# DM1098LUXD-LITE_LEFT_OV7251.net
KiCad netlist of a schematic drawn in Altium Designer
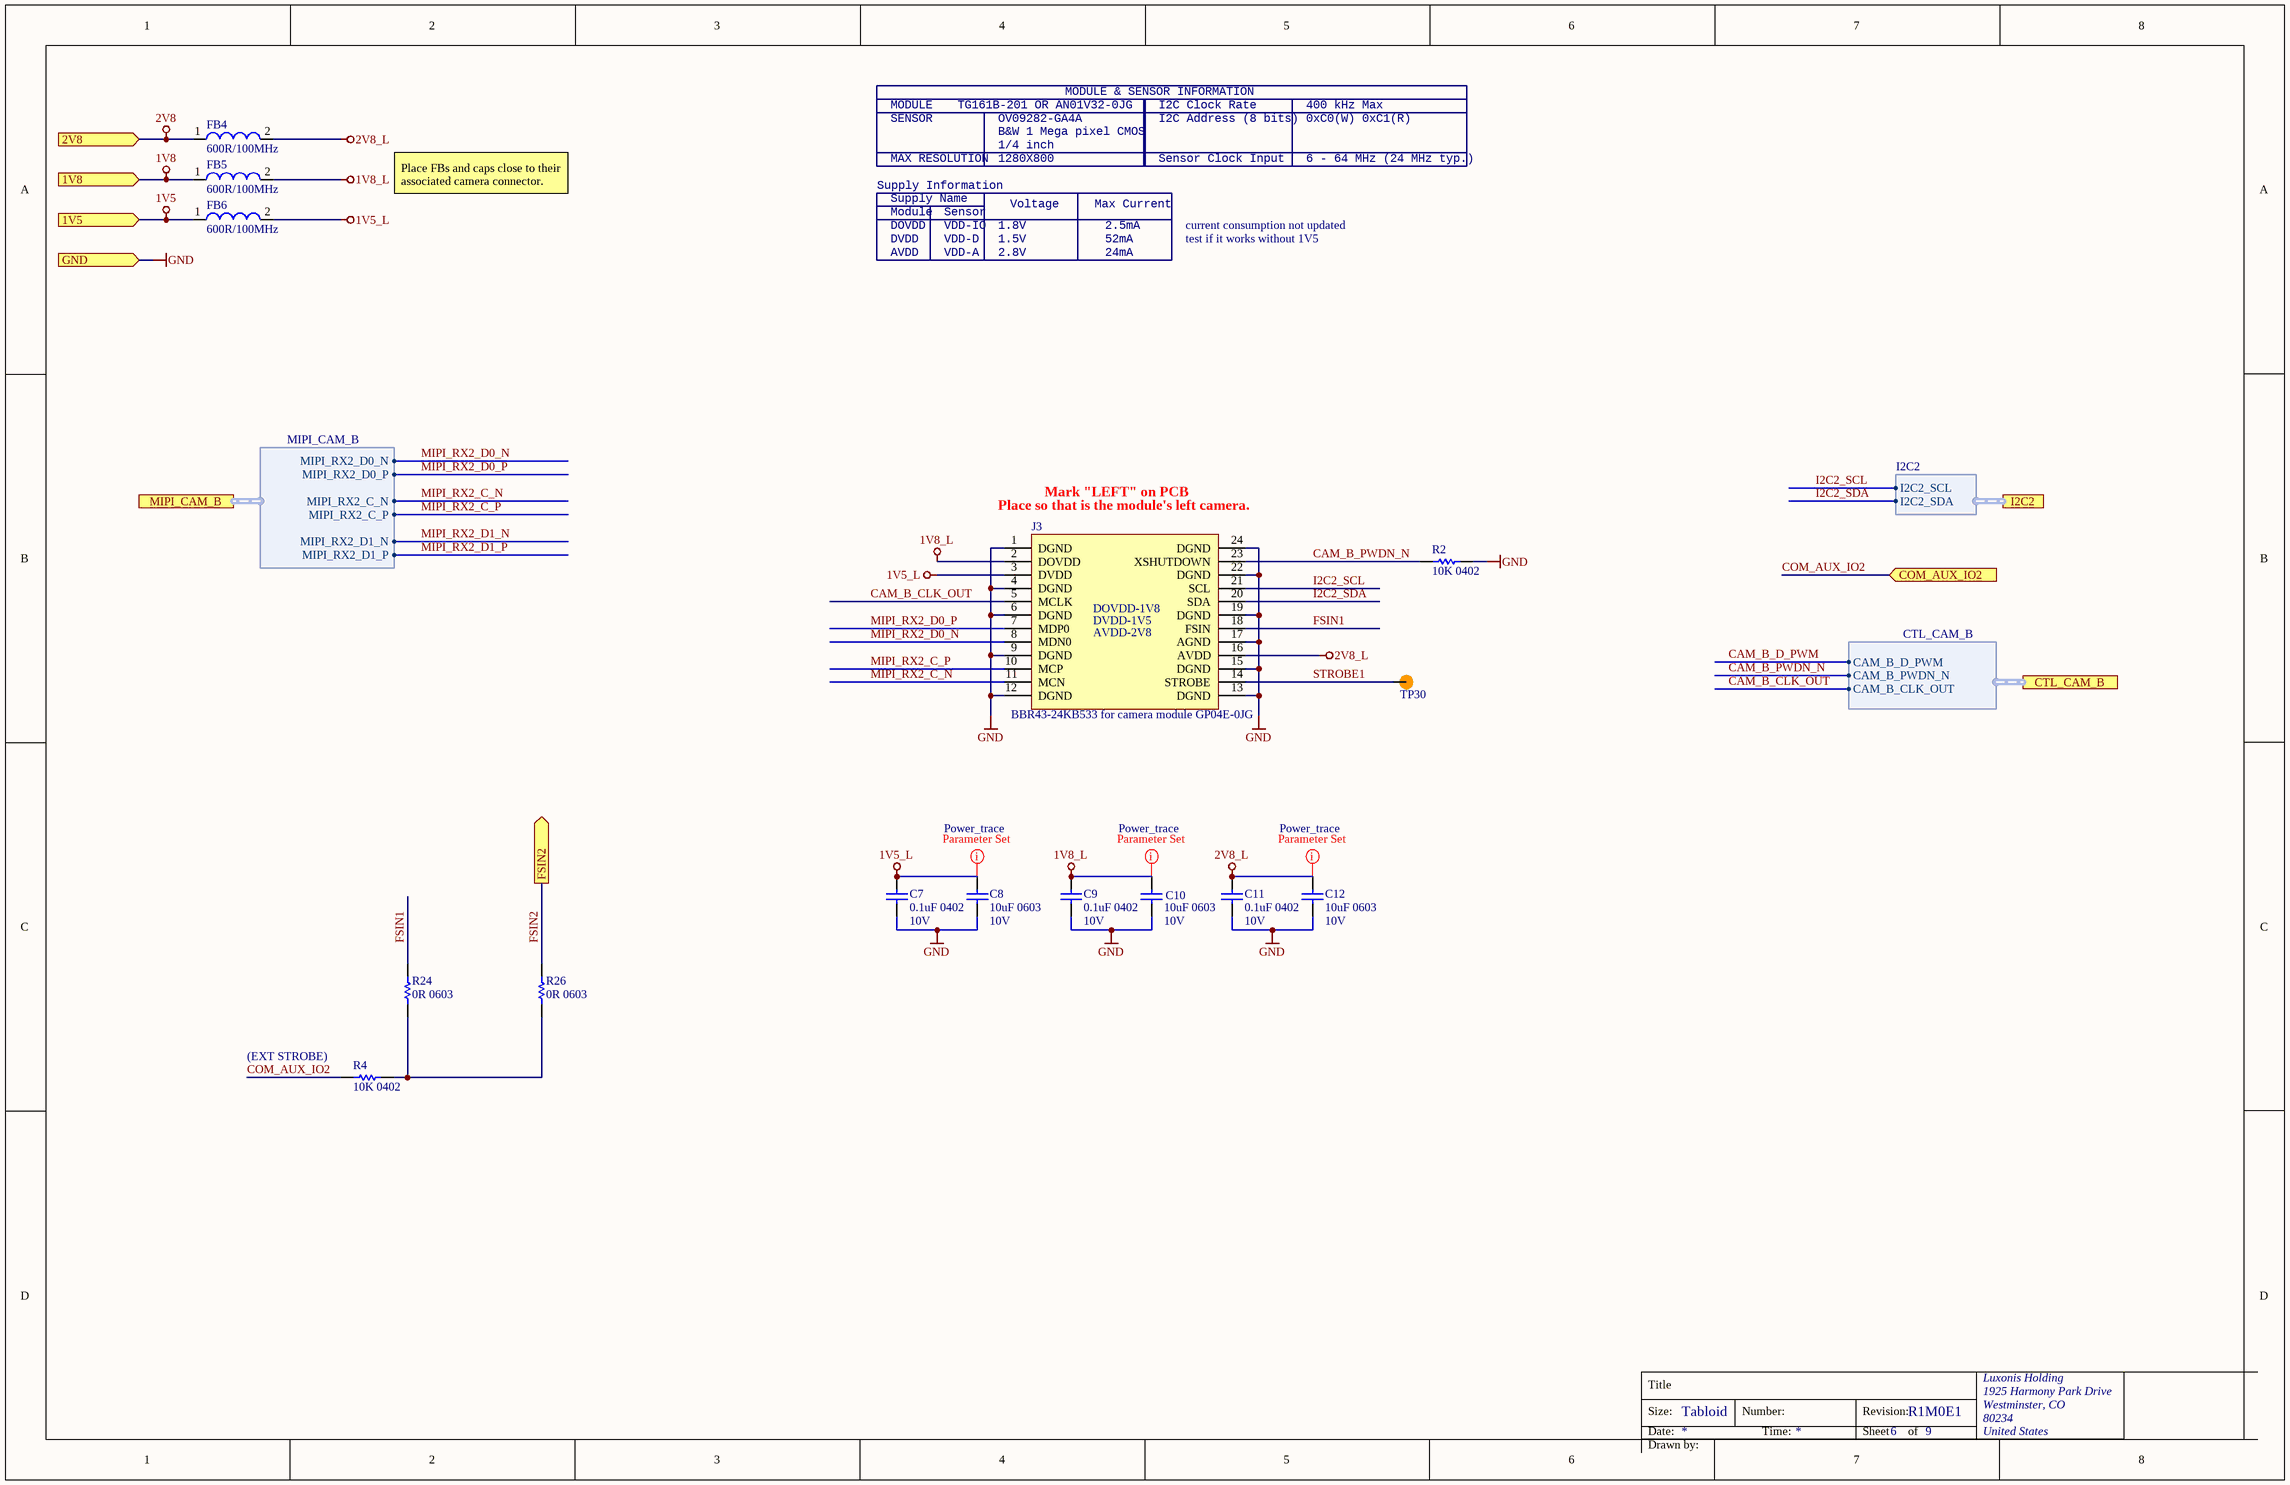
[diagram p0: DM1098LUXD-LITE_LEFT_OV7251.SchDoc]

(export (version "E")
  (design (tool "Eeschema 10.0.6"))
  (components
    (comp (ref "C7")
      (value "0.1uF 0402")
      (footprint "CAP_Altium_Vault_Generic:CAPC0402(1005)70_L")
      (description "CAP CER 0.1UF 10V X7R 0402 5%")
      (fields (field (name "TOLERANCE") "5%") (field (name "VOLTAGE RATING") "10V"))
      (libsource (lib "LuxonisMaster") (part "GRM155R71A104JA01D"))
    )
    (comp (ref "C8")
      (value "10uF 0603")
      (footprint "CAP_Altium_Vault_Generic:CAPC0603(1608)100_L")
      (description "CAP CER 10UF 10V X5R 0603 20%")
      (fields (field (name "TOLERANCE") "20%") (field (name "VOLTAGE RATING") "10V"))
      (libsource (lib "LuxonisMaster") (part "GRM188R61A106ME69D"))
    )
    (comp (ref "C9")
      (value "0.1uF 0402")
      (footprint "CAP_Altium_Vault_Generic:CAPC0402(1005)70_L")
      (description "CAP CER 0.1UF 10V X7R 0402 5%")
      (fields (field (name "TOLERANCE") "5%") (field (name "VOLTAGE RATING") "10V"))
      (libsource (lib "LuxonisMaster") (part "GRM155R71A104JA01D"))
    )
    (comp (ref "C10")
      (value "10uF 0603")
      (footprint "CAP_Altium_Vault_Generic:CAPC0603(1608)100_L")
      (description "CAP CER 10UF 10V X5R 0603 20%")
      (fields (field (name "TOLERANCE") "20%") (field (name "VOLTAGE RATING") "10V"))
      (libsource (lib "LuxonisMaster") (part "GRM188R61A106ME69D"))
    )
    (comp (ref "C11")
      (value "0.1uF 0402")
      (footprint "CAP_Altium_Vault_Generic:CAPC0402(1005)70_L")
      (description "CAP CER 0.1UF 10V X7R 0402 5%")
      (fields (field (name "TOLERANCE") "5%") (field (name "VOLTAGE RATING") "10V"))
      (libsource (lib "LuxonisMaster") (part "GRM155R71A104JA01D"))
    )
    (comp (ref "C12")
      (value "10uF 0603")
      (footprint "CAP_Altium_Vault_Generic:CAPC0603(1608)100_L")
      (description "CAP CER 10UF 10V X5R 0603 20%")
      (fields (field (name "TOLERANCE") "20%") (field (name "VOLTAGE RATING") "10V"))
      (libsource (lib "LuxonisMaster") (part "GRM188R61A106ME69D"))
    )
    (comp (ref "FB4")
      (value "600R/100MHz")
      (footprint "LuxonisMaster:2508056017Y2")
      (description "FERRITE BEAD, 0.1OHM, 2A, 0805, 600R/100MHz")
      (fields (field (name "TOLERANCE") "25%"))
      (libsource (lib "LuxonisMaster") (part "2508056017Y2"))
    )
    (comp (ref "FB5")
      (value "600R/100MHz")
      (footprint "LuxonisMaster:2508056017Y2")
      (description "FERRITE BEAD, 0.1OHM, 2A, 0805, 600R/100MHz")
      (fields (field (name "TOLERANCE") "25%"))
      (libsource (lib "LuxonisMaster") (part "2508056017Y2"))
    )
    (comp (ref "FB6")
      (value "600R/100MHz")
      (footprint "LuxonisMaster:2508056017Y2")
      (description "FERRITE BEAD, 0.1OHM, 2A, 0805, 600R/100MHz")
      (fields (field (name "TOLERANCE") "25%"))
      (libsource (lib "LuxonisMaster") (part "2508056017Y2"))
    )
    (comp (ref "J3")
      (value "BBR43-24KB533 for camera module GP04E-0JG")
      (footprint "GP04E-0JG OV7251")
      (description "CONN 24 way, 2 row board to board connector SMD")
      (libsource (lib "DM1098LUXD-LITE") (part "GP04E-0JG_Connector"))
    )
    (comp (ref "R2")
      (value "10K 0402")
      (footprint "RES_Altium_Vault_Generic:RESC0402(1005)_L")
      (fields (field (name "TOLERANCE") "1%"))
      (libsource (lib "LuxonisMaster") (part "RC0402FR-1310KL"))
    )
    (comp (ref "R4")
      (value "10K 0402")
      (footprint "RES_Altium_Vault_Generic:RESC0402(1005)_L")
      (fields (field (name "TOLERANCE") "1%"))
      (libsource (lib "LuxonisMaster") (part "RC0402FR-1310KL"))
    )
    (comp (ref "R24")
      (value "0R 0603")
      (footprint "RES_Altium_Vault_Generic:RESC0603(1608)_N")
      (fields (field (name "TOLERANCE") "5%"))
      (libsource (lib "LuxonisMaster") (part "CRCW06030000Z0EA"))
    )
    (comp (ref "R26")
      (value "0R 0603")
      (footprint "RES_Altium_Vault_Generic:RESC0603(1608)_N")
      (fields (field (name "TOLERANCE") "5%"))
      (libsource (lib "LuxonisMaster") (part "CRCW06030000Z0EA"))
    )
    (comp (ref "TP30")
      (value "TP100_200_NS")
      (footprint "LuxonisMaster:TP100_200_NS")
      (libsource (lib "LuxonisMaster") (part "TEST_POINT"))
    )
  )
  (nets
    (net (code "4") (name "/CAM_B_CLK_OUT") (class "Default")
      (node (ref "J3") (pin "5") (pinfunction "MCLK_5") (pintype "passive"))
    )
    (net (code "6") (name "/CAM_B_PWDN_N") (class "Default")
      (node (ref "J3") (pin "23") (pinfunction "XSHUTDOWN_23") (pintype "passive"))
      (node (ref "R2") (pin "1") (pinfunction "1_1") (pintype "passive"))
    )
    (net (code "7") (name "/COM_AUX_IO2") (class "Default")
      (node (ref "R4") (pin "1") (pinfunction "1_1") (pintype "passive"))
    )
    (net (code "8") (name "/FSIN1") (class "Default")
      (node (ref "J3") (pin "18") (pinfunction "FSIN_18") (pintype "passive"))
      (node (ref "R24") (pin "2") (pinfunction "2_2") (pintype "passive"))
    )
    (net (code "9") (name "/FSIN2") (class "Default")
      (node (ref "R26") (pin "2") (pinfunction "2_2") (pintype "passive"))
    )
    (net (code "10") (name "/I2C2_SCL") (class "Default")
      (node (ref "J3") (pin "21") (pinfunction "SCL_21") (pintype "passive"))
    )
    (net (code "11") (name "/I2C2_SDA") (class "Default")
      (node (ref "J3") (pin "20") (pinfunction "SDA_20") (pintype "passive"))
    )
    (net (code "12") (name "/MIPI_RX2_C_N") (class "Default")
      (node (ref "J3") (pin "11") (pinfunction "MCN_11") (pintype "passive"))
    )
    (net (code "13") (name "/MIPI_RX2_C_P") (class "Default")
      (node (ref "J3") (pin "10") (pinfunction "MCP_10") (pintype "passive"))
    )
    (net (code "14") (name "/MIPI_RX2_D0_N") (class "Default")
      (node (ref "J3") (pin "8") (pinfunction "MDN0_8") (pintype "passive"))
    )
    (net (code "15") (name "/MIPI_RX2_D0_P") (class "Default")
      (node (ref "J3") (pin "7") (pinfunction "MDP0_7") (pintype "passive"))
    )
    (net (code "18") (name "/STROBE1") (class "Default")
      (node (ref "J3") (pin "14") (pinfunction "STROBE_14") (pintype "passive"))
      (node (ref "TP30") (pin "1") (pintype "passive"))
    )
    (net (code "22") (name "1V5") (class "Default")
      (node (ref "FB6") (pin "1") (pinfunction "1_1") (pintype "passive"))
    )
    (net (code "23") (name "1V5_L") (class "Default")
      (node (ref "C7") (pin "2") (pinfunction "2_2") (pintype "passive"))
      (node (ref "C8") (pin "2") (pinfunction "2_2") (pintype "passive"))
      (node (ref "FB6") (pin "2") (pinfunction "2_2") (pintype "passive"))
      (node (ref "J3") (pin "3") (pinfunction "DVDD_3") (pintype "passive"))
    )
    (net (code "24") (name "1V8") (class "Default")
      (node (ref "FB5") (pin "1") (pinfunction "1_1") (pintype "passive"))
    )
    (net (code "25") (name "1V8_L") (class "Default")
      (node (ref "C10") (pin "2") (pinfunction "2_2") (pintype "passive"))
      (node (ref "C9") (pin "2") (pinfunction "2_2") (pintype "passive"))
      (node (ref "FB5") (pin "2") (pinfunction "2_2") (pintype "passive"))
      (node (ref "J3") (pin "2") (pinfunction "DOVDD_2") (pintype "passive"))
    )
    (net (code "26") (name "2V8") (class "Default")
      (node (ref "FB4") (pin "1") (pinfunction "1_1") (pintype "passive"))
    )
    (net (code "27") (name "2V8_L") (class "Default")
      (node (ref "C11") (pin "2") (pinfunction "2_2") (pintype "passive"))
      (node (ref "C12") (pin "2") (pinfunction "2_2") (pintype "passive"))
      (node (ref "FB4") (pin "2") (pinfunction "2_2") (pintype "passive"))
      (node (ref "J3") (pin "16") (pinfunction "AVDD_16") (pintype "passive"))
    )
    (net (code "28") (name "GND") (class "Default")
      (node (ref "C10") (pin "1") (pinfunction "1_1") (pintype "passive"))
      (node (ref "C11") (pin "1") (pinfunction "1_1") (pintype "passive"))
      (node (ref "C12") (pin "1") (pinfunction "1_1") (pintype "passive"))
      (node (ref "C7") (pin "1") (pinfunction "1_1") (pintype "passive"))
      (node (ref "C8") (pin "1") (pinfunction "1_1") (pintype "passive"))
      (node (ref "C9") (pin "1") (pinfunction "1_1") (pintype "passive"))
      (node (ref "J3") (pin "1") (pinfunction "DGND_1") (pintype "passive"))
      (node (ref "J3") (pin "12") (pinfunction "DGND_12") (pintype "passive"))
      (node (ref "J3") (pin "13") (pinfunction "DGND_13") (pintype "passive"))
      (node (ref "J3") (pin "15") (pinfunction "DGND_15") (pintype "passive"))
      (node (ref "J3") (pin "17") (pinfunction "AGND_17") (pintype "passive"))
      (node (ref "J3") (pin "19") (pinfunction "DGND_19") (pintype "passive"))
      (node (ref "J3") (pin "22") (pinfunction "DGND_22") (pintype "passive"))
      (node (ref "J3") (pin "24") (pinfunction "DGND_24") (pintype "passive"))
      (node (ref "J3") (pin "4") (pinfunction "DGND_4") (pintype "passive"))
      (node (ref "J3") (pin "6") (pinfunction "DGND_6") (pintype "passive"))
      (node (ref "J3") (pin "9") (pinfunction "DGND_9") (pintype "passive"))
      (node (ref "R2") (pin "2") (pinfunction "2_2") (pintype "passive"))
    )
    (net (code "29") (name "Net-(R24-Pad1)") (class "Default")
      (node (ref "R24") (pin "1") (pinfunction "1_1") (pintype "passive"))
      (node (ref "R26") (pin "1") (pinfunction "1_1") (pintype "passive"))
      (node (ref "R4") (pin "2") (pinfunction "2_2") (pintype "passive"))
    )
  )
)
